# Decoder_ROMS.net
KiCad netlist of a schematic drawn in EAGLE
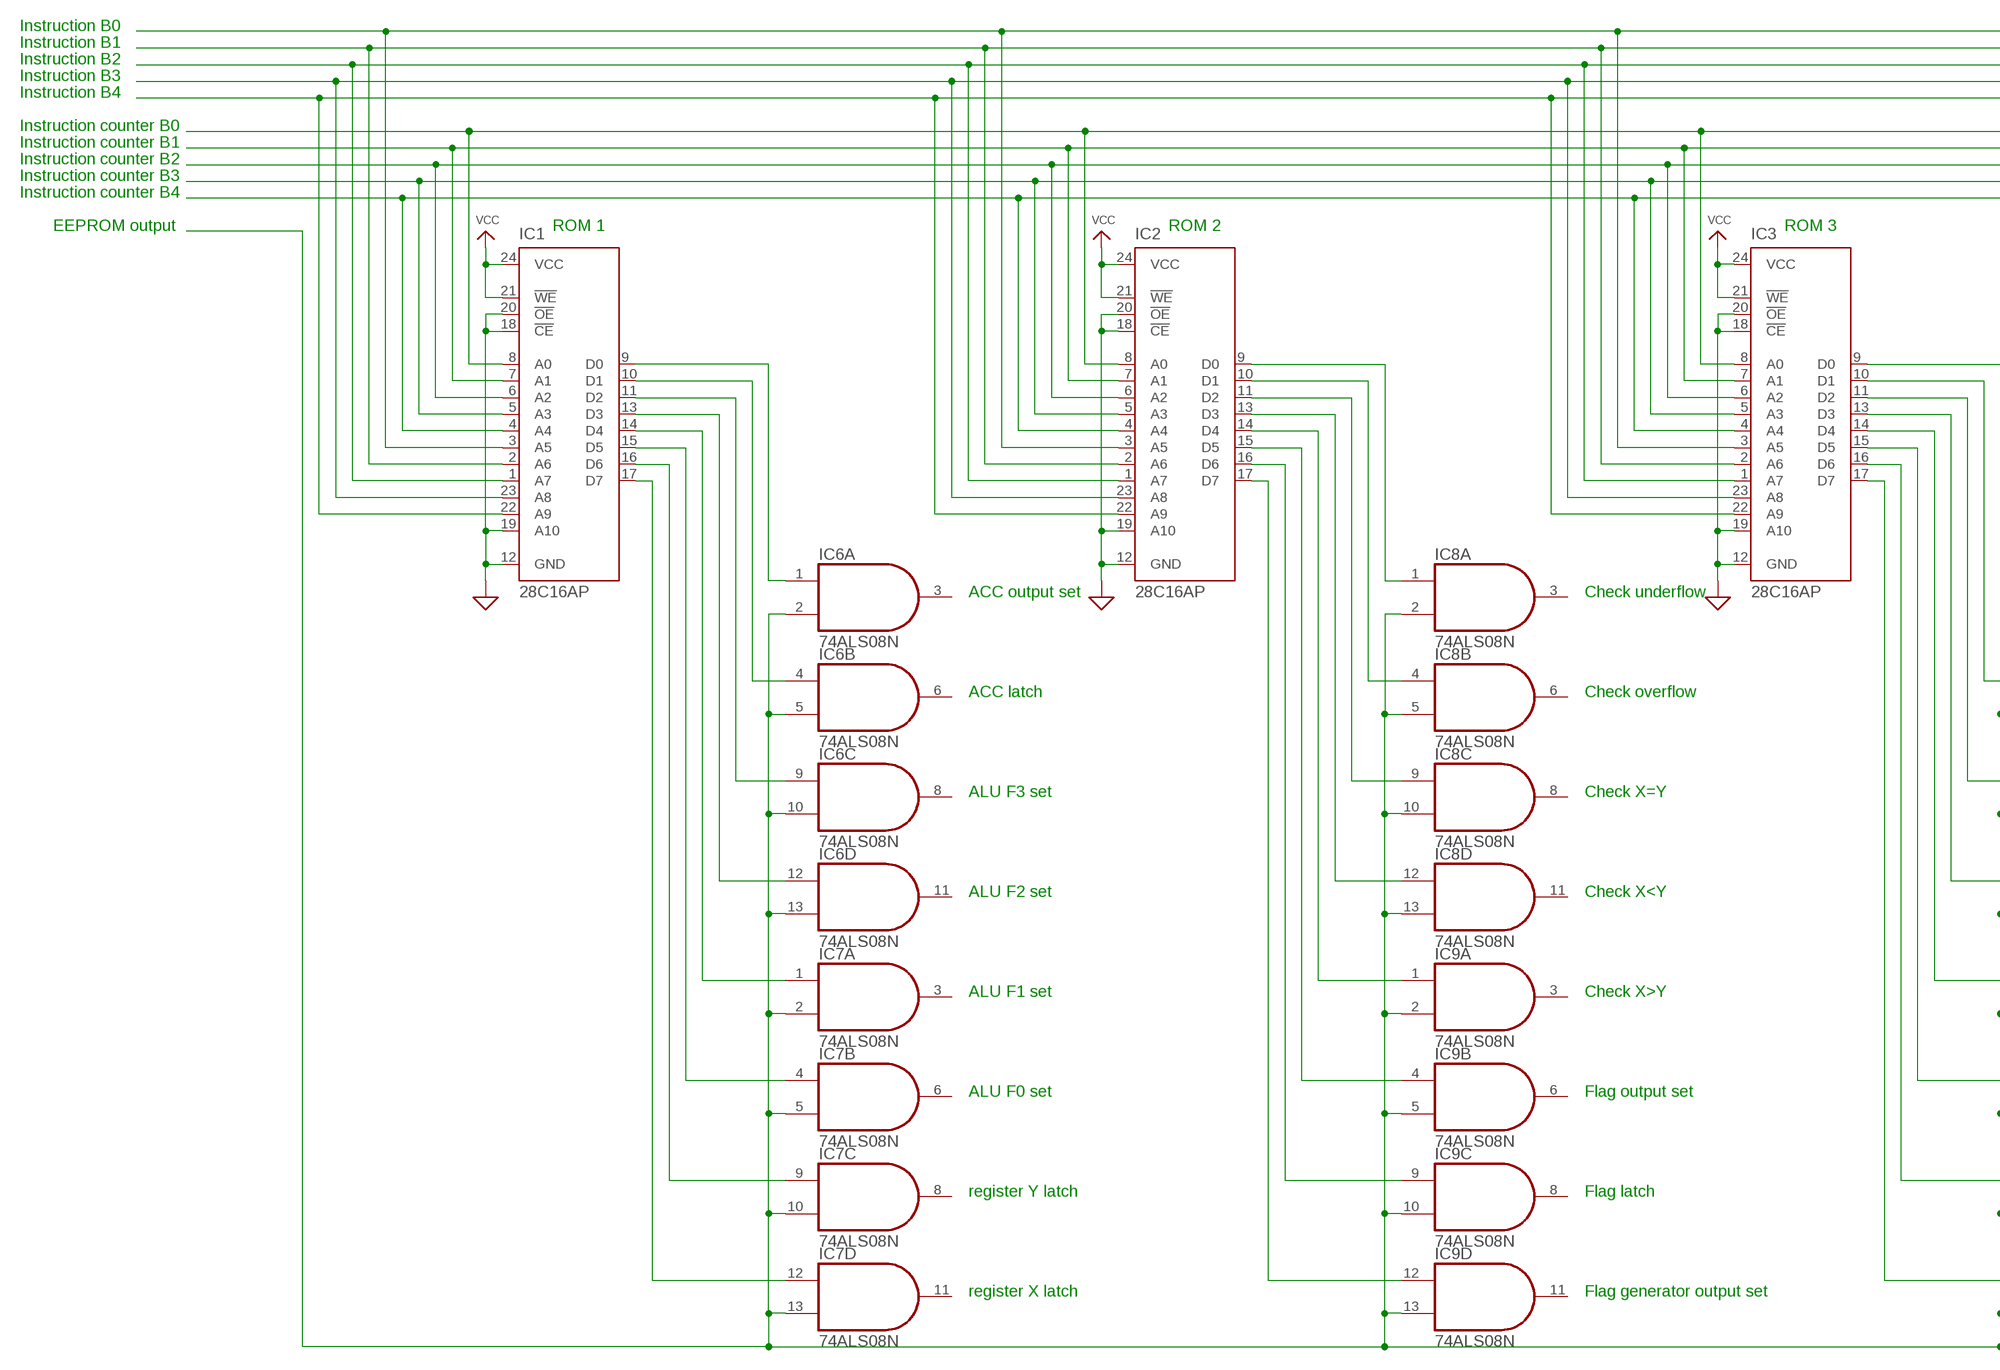
[diagram p0: schematic, sheet 1, part 1 of 2]
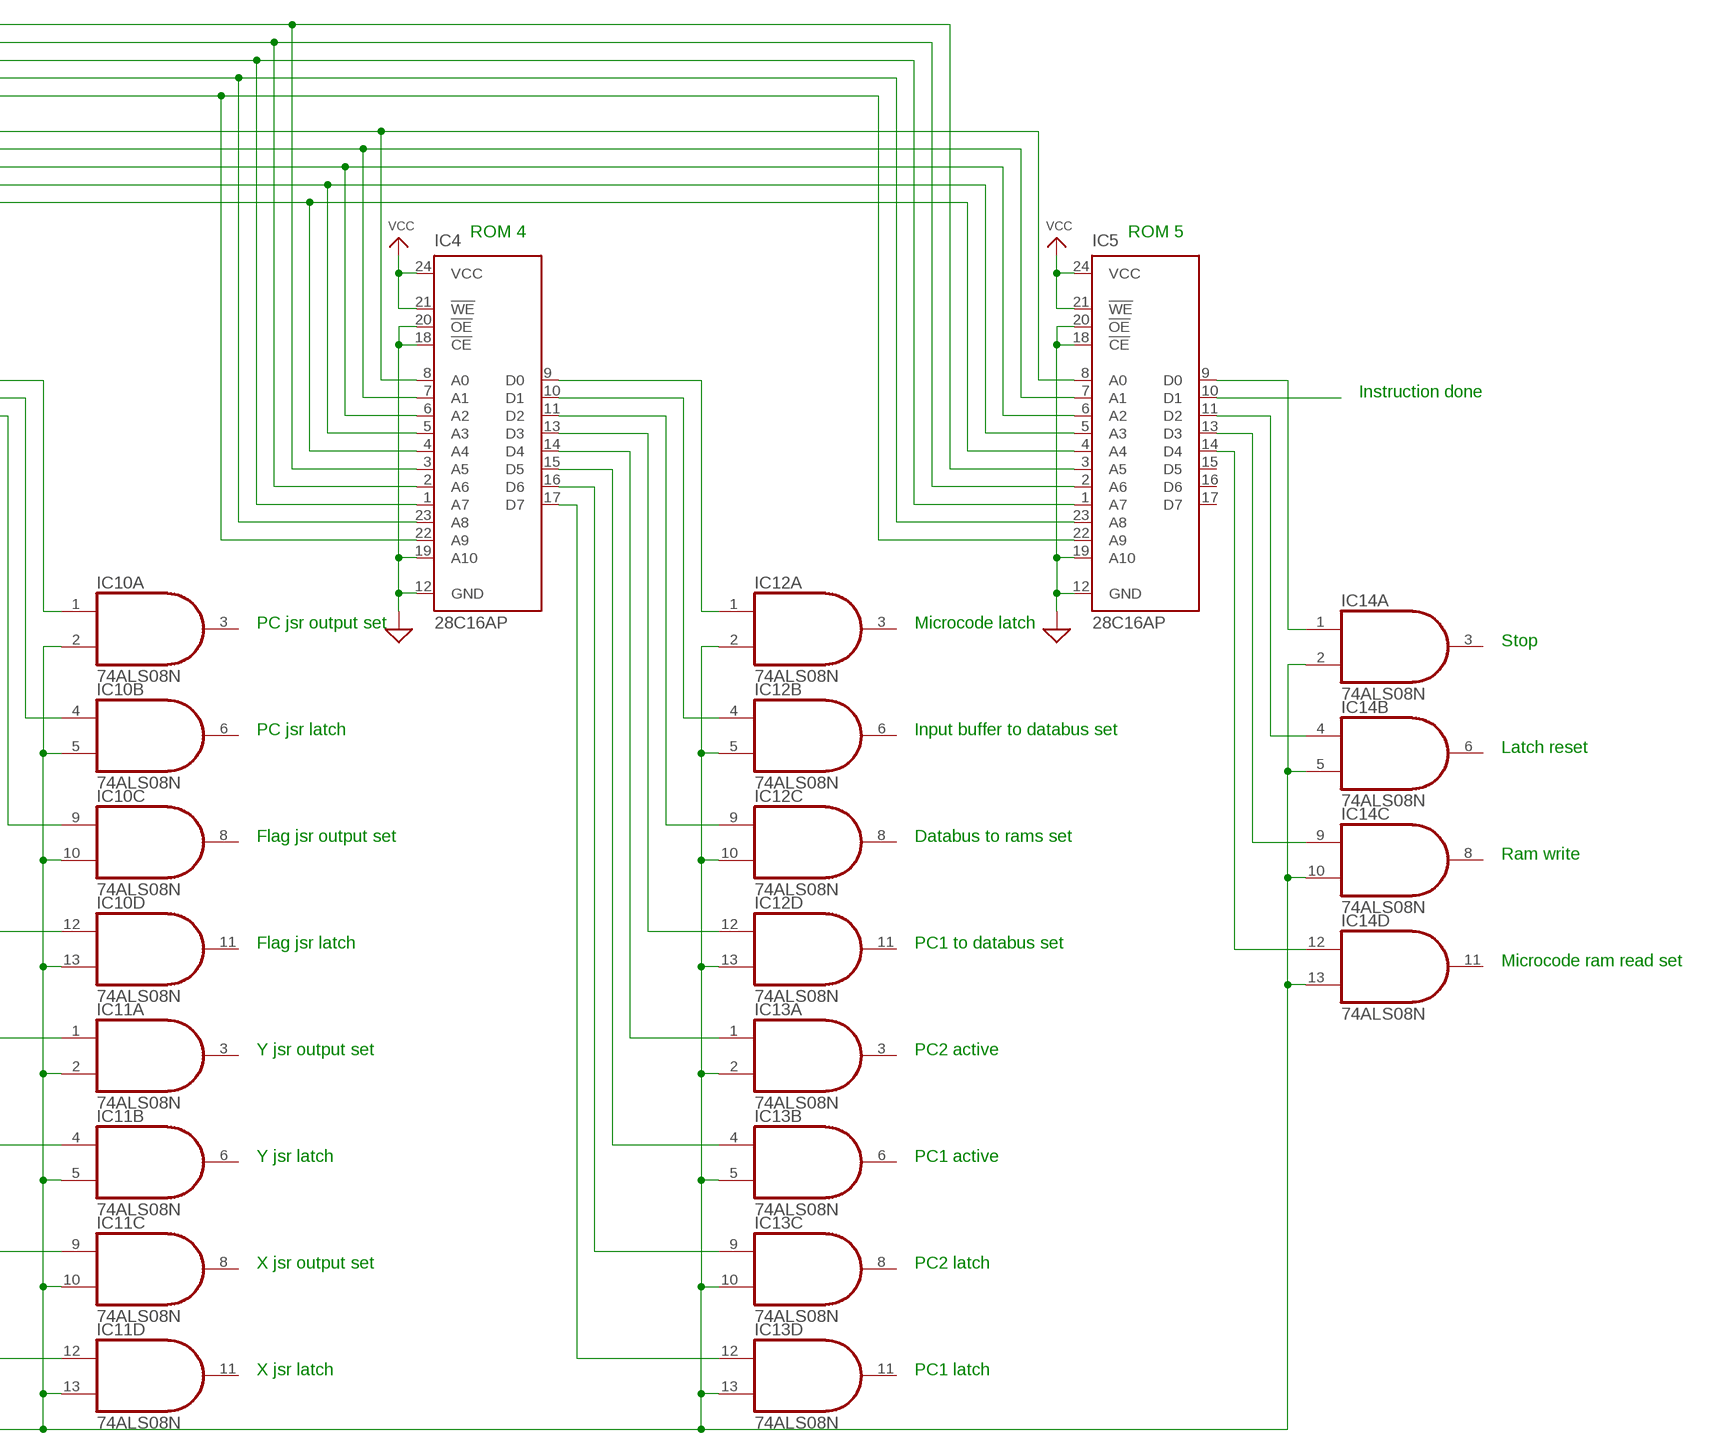
[diagram p1: schematic, sheet 1, part 2 of 2]

(export (version "E")
  (design (tool "Eeschema 10.0.6"))
  (components
    (comp (ref "IC1")
      (value "28C16AP")
      (footprint "eagle-import:DIL24-6")
      (fields (field (name "MPN") "CAT28C16ALI-12"))
      (libsource (lib "eagle-import") (part "2816APC"))
    )
    (comp (ref "IC2")
      (value "28C16AP")
      (footprint "eagle-import:DIL24-6")
      (fields (field (name "MPN") "CAT28C16ALI-12"))
      (libsource (lib "eagle-import") (part "2816APC"))
    )
    (comp (ref "IC3")
      (value "28C16AP")
      (footprint "eagle-import:DIL24-6")
      (fields (field (name "MPN") "CAT28C16ALI-12"))
      (libsource (lib "eagle-import") (part "2816APC"))
    )
    (comp (ref "IC4")
      (value "28C16AP")
      (footprint "eagle-import:DIL24-6")
      (fields (field (name "MPN") "CAT28C16ALI-12"))
      (libsource (lib "eagle-import") (part "2816APC"))
    )
    (comp (ref "IC5")
      (value "28C16AP")
      (footprint "eagle-import:DIL24-6")
      (fields (field (name "MPN") "CAT28C16ALI-12"))
      (libsource (lib "eagle-import") (part "2816APC"))
    )
    (comp (ref "IC6")
      (value "74ALS08N")
      (footprint "eagle-import:DIL14")
      (libsource (lib "eagle-import") (part "7408NALS"))
    )
    (comp (ref "IC7")
      (value "74ALS08N")
      (footprint "eagle-import:DIL14")
      (libsource (lib "eagle-import") (part "7408NALS"))
    )
    (comp (ref "IC8")
      (value "74ALS08N")
      (footprint "eagle-import:DIL14")
      (libsource (lib "eagle-import") (part "7408NALS"))
    )
    (comp (ref "IC9")
      (value "74ALS08N")
      (footprint "eagle-import:DIL14")
      (libsource (lib "eagle-import") (part "7408NALS"))
    )
    (comp (ref "IC10")
      (value "74ALS08N")
      (footprint "eagle-import:DIL14")
      (libsource (lib "eagle-import") (part "7408NALS"))
    )
    (comp (ref "IC11")
      (value "74ALS08N")
      (footprint "eagle-import:DIL14")
      (libsource (lib "eagle-import") (part "7408NALS"))
    )
    (comp (ref "IC12")
      (value "74ALS08N")
      (footprint "eagle-import:DIL14")
      (libsource (lib "eagle-import") (part "7408NALS"))
    )
    (comp (ref "IC13")
      (value "74ALS08N")
      (footprint "eagle-import:DIL14")
      (libsource (lib "eagle-import") (part "7408NALS"))
    )
    (comp (ref "IC14")
      (value "74ALS08N")
      (footprint "eagle-import:DIL14")
      (libsource (lib "eagle-import") (part "7408NALS"))
    )
  )
  (nets
    (net (code "1") (name "Net-(IC1-A0)") (class "Default")
      (node (ref "IC1") (pin "8") (pinfunction "A0_8") (pintype "input"))
      (node (ref "IC2") (pin "8") (pinfunction "A0_8") (pintype "input"))
      (node (ref "IC3") (pin "8") (pinfunction "A0_8") (pintype "input"))
      (node (ref "IC4") (pin "8") (pinfunction "A0_8") (pintype "input"))
      (node (ref "IC5") (pin "8") (pinfunction "A0_8") (pintype "input"))
    )
    (net (code "2") (name "Net-(IC1-A1)") (class "Default")
      (node (ref "IC1") (pin "7") (pinfunction "A1_7") (pintype "input"))
      (node (ref "IC2") (pin "7") (pinfunction "A1_7") (pintype "input"))
      (node (ref "IC3") (pin "7") (pinfunction "A1_7") (pintype "input"))
      (node (ref "IC4") (pin "7") (pinfunction "A1_7") (pintype "input"))
      (node (ref "IC5") (pin "7") (pinfunction "A1_7") (pintype "input"))
    )
    (net (code "3") (name "Net-(IC1-A2)") (class "Default")
      (node (ref "IC1") (pin "6") (pinfunction "A2_6") (pintype "input"))
      (node (ref "IC2") (pin "6") (pinfunction "A2_6") (pintype "input"))
      (node (ref "IC3") (pin "6") (pinfunction "A2_6") (pintype "input"))
      (node (ref "IC4") (pin "6") (pinfunction "A2_6") (pintype "input"))
      (node (ref "IC5") (pin "6") (pinfunction "A2_6") (pintype "input"))
    )
    (net (code "4") (name "Net-(IC1-A3)") (class "Default")
      (node (ref "IC1") (pin "5") (pinfunction "A3_5") (pintype "input"))
      (node (ref "IC2") (pin "5") (pinfunction "A3_5") (pintype "input"))
      (node (ref "IC3") (pin "5") (pinfunction "A3_5") (pintype "input"))
      (node (ref "IC4") (pin "5") (pinfunction "A3_5") (pintype "input"))
      (node (ref "IC5") (pin "5") (pinfunction "A3_5") (pintype "input"))
    )
    (net (code "5") (name "Net-(IC1-A4)") (class "Default")
      (node (ref "IC1") (pin "4") (pinfunction "A4_4") (pintype "input"))
      (node (ref "IC2") (pin "4") (pinfunction "A4_4") (pintype "input"))
      (node (ref "IC3") (pin "4") (pinfunction "A4_4") (pintype "input"))
      (node (ref "IC4") (pin "4") (pinfunction "A4_4") (pintype "input"))
      (node (ref "IC5") (pin "4") (pinfunction "A4_4") (pintype "input"))
    )
    (net (code "6") (name "Net-(IC1-A5)") (class "Default")
      (node (ref "IC1") (pin "3") (pinfunction "A5_3") (pintype "input"))
      (node (ref "IC2") (pin "3") (pinfunction "A5_3") (pintype "input"))
      (node (ref "IC3") (pin "3") (pinfunction "A5_3") (pintype "input"))
      (node (ref "IC4") (pin "3") (pinfunction "A5_3") (pintype "input"))
      (node (ref "IC5") (pin "3") (pinfunction "A5_3") (pintype "input"))
    )
    (net (code "7") (name "Net-(IC1-A6)") (class "Default")
      (node (ref "IC1") (pin "2") (pinfunction "A6_2") (pintype "input"))
      (node (ref "IC2") (pin "2") (pinfunction "A6_2") (pintype "input"))
      (node (ref "IC3") (pin "2") (pinfunction "A6_2") (pintype "input"))
      (node (ref "IC4") (pin "2") (pinfunction "A6_2") (pintype "input"))
      (node (ref "IC5") (pin "2") (pinfunction "A6_2") (pintype "input"))
    )
    (net (code "8") (name "Net-(IC1-A7)") (class "Default")
      (node (ref "IC1") (pin "1") (pinfunction "A7_1") (pintype "input"))
      (node (ref "IC2") (pin "1") (pinfunction "A7_1") (pintype "input"))
      (node (ref "IC3") (pin "1") (pinfunction "A7_1") (pintype "input"))
      (node (ref "IC4") (pin "1") (pinfunction "A7_1") (pintype "input"))
      (node (ref "IC5") (pin "1") (pinfunction "A7_1") (pintype "input"))
    )
    (net (code "9") (name "Net-(IC1-A8)") (class "Default")
      (node (ref "IC1") (pin "23") (pinfunction "A8_23") (pintype "input"))
      (node (ref "IC2") (pin "23") (pinfunction "A8_23") (pintype "input"))
      (node (ref "IC3") (pin "23") (pinfunction "A8_23") (pintype "input"))
      (node (ref "IC4") (pin "23") (pinfunction "A8_23") (pintype "input"))
      (node (ref "IC5") (pin "23") (pinfunction "A8_23") (pintype "input"))
    )
    (net (code "10") (name "Net-(IC1-A9)") (class "Default")
      (node (ref "IC1") (pin "22") (pinfunction "A9_22") (pintype "input"))
      (node (ref "IC2") (pin "22") (pinfunction "A9_22") (pintype "input"))
      (node (ref "IC3") (pin "22") (pinfunction "A9_22") (pintype "input"))
      (node (ref "IC4") (pin "22") (pinfunction "A9_22") (pintype "input"))
      (node (ref "IC5") (pin "22") (pinfunction "A9_22") (pintype "input"))
    )
    (net (code "11") (name "Net-(IC1-D0)") (class "Default")
      (node (ref "IC1") (pin "9") (pinfunction "D0_9") (pintype "tri_state"))
      (node (ref "IC6") (pin "1") (pinfunction "I0_1") (pintype "input"))
    )
    (net (code "12") (name "Net-(IC1-D1)") (class "Default")
      (node (ref "IC1") (pin "10") (pinfunction "D1_10") (pintype "tri_state"))
      (node (ref "IC6") (pin "4") (pinfunction "I0_4") (pintype "input"))
    )
    (net (code "13") (name "Net-(IC1-D2)") (class "Default")
      (node (ref "IC1") (pin "11") (pinfunction "D2_11") (pintype "tri_state"))
      (node (ref "IC6") (pin "9") (pinfunction "I0_9") (pintype "input"))
    )
    (net (code "14") (name "Net-(IC1-D3)") (class "Default")
      (node (ref "IC1") (pin "13") (pinfunction "D3_13") (pintype "tri_state"))
      (node (ref "IC6") (pin "12") (pinfunction "I0_12") (pintype "input"))
    )
    (net (code "15") (name "Net-(IC1-D4)") (class "Default")
      (node (ref "IC1") (pin "14") (pinfunction "D4_14") (pintype "tri_state"))
      (node (ref "IC7") (pin "1") (pinfunction "I0_1") (pintype "input"))
    )
    (net (code "16") (name "Net-(IC1-D5)") (class "Default")
      (node (ref "IC1") (pin "15") (pinfunction "D5_15") (pintype "tri_state"))
      (node (ref "IC7") (pin "4") (pinfunction "I0_4") (pintype "input"))
    )
    (net (code "17") (name "Net-(IC1-D6)") (class "Default")
      (node (ref "IC1") (pin "16") (pinfunction "D6_16") (pintype "tri_state"))
      (node (ref "IC7") (pin "9") (pinfunction "I0_9") (pintype "input"))
    )
    (net (code "18") (name "Net-(IC1-D7)") (class "Default")
      (node (ref "IC1") (pin "17") (pinfunction "D7_17") (pintype "tri_state"))
      (node (ref "IC7") (pin "12") (pinfunction "I0_12") (pintype "input"))
    )
    (net (code "19") (name "Net-(IC2-D0)") (class "Default")
      (node (ref "IC2") (pin "9") (pinfunction "D0_9") (pintype "tri_state"))
      (node (ref "IC8") (pin "1") (pinfunction "I0_1") (pintype "input"))
    )
    (net (code "20") (name "Net-(IC2-D1)") (class "Default")
      (node (ref "IC2") (pin "10") (pinfunction "D1_10") (pintype "tri_state"))
      (node (ref "IC8") (pin "4") (pinfunction "I0_4") (pintype "input"))
    )
    (net (code "21") (name "Net-(IC2-D2)") (class "Default")
      (node (ref "IC2") (pin "11") (pinfunction "D2_11") (pintype "tri_state"))
      (node (ref "IC8") (pin "9") (pinfunction "I0_9") (pintype "input"))
    )
    (net (code "22") (name "Net-(IC2-D3)") (class "Default")
      (node (ref "IC2") (pin "13") (pinfunction "D3_13") (pintype "tri_state"))
      (node (ref "IC8") (pin "12") (pinfunction "I0_12") (pintype "input"))
    )
    (net (code "23") (name "Net-(IC2-D4)") (class "Default")
      (node (ref "IC2") (pin "14") (pinfunction "D4_14") (pintype "tri_state"))
      (node (ref "IC9") (pin "1") (pinfunction "I0_1") (pintype "input"))
    )
    (net (code "24") (name "Net-(IC2-D5)") (class "Default")
      (node (ref "IC2") (pin "15") (pinfunction "D5_15") (pintype "tri_state"))
      (node (ref "IC9") (pin "4") (pinfunction "I0_4") (pintype "input"))
    )
    (net (code "25") (name "Net-(IC2-D6)") (class "Default")
      (node (ref "IC2") (pin "16") (pinfunction "D6_16") (pintype "tri_state"))
      (node (ref "IC9") (pin "9") (pinfunction "I0_9") (pintype "input"))
    )
    (net (code "26") (name "Net-(IC2-D7)") (class "Default")
      (node (ref "IC2") (pin "17") (pinfunction "D7_17") (pintype "tri_state"))
      (node (ref "IC9") (pin "12") (pinfunction "I0_12") (pintype "input"))
    )
    (net (code "27") (name "Net-(IC10A-I0)") (class "Default")
      (node (ref "IC10") (pin "1") (pinfunction "I0_1") (pintype "input"))
      (node (ref "IC3") (pin "9") (pinfunction "D0_9") (pintype "tri_state"))
    )
    (net (code "28") (name "Net-(IC10A-I1)") (class "Default")
      (node (ref "IC10") (pin "10") (pinfunction "I1_10") (pintype "input"))
      (node (ref "IC10") (pin "13") (pinfunction "I1_13") (pintype "input"))
      (node (ref "IC10") (pin "2") (pinfunction "I1_2") (pintype "input"))
      (node (ref "IC10") (pin "5") (pinfunction "I1_5") (pintype "input"))
      (node (ref "IC11") (pin "10") (pinfunction "I1_10") (pintype "input"))
      (node (ref "IC11") (pin "13") (pinfunction "I1_13") (pintype "input"))
      (node (ref "IC11") (pin "2") (pinfunction "I1_2") (pintype "input"))
      (node (ref "IC11") (pin "5") (pinfunction "I1_5") (pintype "input"))
      (node (ref "IC12") (pin "10") (pinfunction "I1_10") (pintype "input"))
      (node (ref "IC12") (pin "13") (pinfunction "I1_13") (pintype "input"))
      (node (ref "IC12") (pin "2") (pinfunction "I1_2") (pintype "input"))
      (node (ref "IC12") (pin "5") (pinfunction "I1_5") (pintype "input"))
      (node (ref "IC13") (pin "10") (pinfunction "I1_10") (pintype "input"))
      (node (ref "IC13") (pin "13") (pinfunction "I1_13") (pintype "input"))
      (node (ref "IC13") (pin "2") (pinfunction "I1_2") (pintype "input"))
      (node (ref "IC13") (pin "5") (pinfunction "I1_5") (pintype "input"))
      (node (ref "IC14") (pin "10") (pinfunction "I1_10") (pintype "input"))
      (node (ref "IC14") (pin "13") (pinfunction "I1_13") (pintype "input"))
      (node (ref "IC14") (pin "2") (pinfunction "I1_2") (pintype "input"))
      (node (ref "IC14") (pin "5") (pinfunction "I1_5") (pintype "input"))
      (node (ref "IC6") (pin "10") (pinfunction "I1_10") (pintype "input"))
      (node (ref "IC6") (pin "13") (pinfunction "I1_13") (pintype "input"))
      (node (ref "IC6") (pin "2") (pinfunction "I1_2") (pintype "input"))
      (node (ref "IC6") (pin "5") (pinfunction "I1_5") (pintype "input"))
      (node (ref "IC7") (pin "10") (pinfunction "I1_10") (pintype "input"))
      (node (ref "IC7") (pin "13") (pinfunction "I1_13") (pintype "input"))
      (node (ref "IC7") (pin "2") (pinfunction "I1_2") (pintype "input"))
      (node (ref "IC7") (pin "5") (pinfunction "I1_5") (pintype "input"))
      (node (ref "IC8") (pin "10") (pinfunction "I1_10") (pintype "input"))
      (node (ref "IC8") (pin "13") (pinfunction "I1_13") (pintype "input"))
      (node (ref "IC8") (pin "2") (pinfunction "I1_2") (pintype "input"))
      (node (ref "IC8") (pin "5") (pinfunction "I1_5") (pintype "input"))
      (node (ref "IC9") (pin "10") (pinfunction "I1_10") (pintype "input"))
      (node (ref "IC9") (pin "13") (pinfunction "I1_13") (pintype "input"))
      (node (ref "IC9") (pin "2") (pinfunction "I1_2") (pintype "input"))
      (node (ref "IC9") (pin "5") (pinfunction "I1_5") (pintype "input"))
    )
    (net (code "29") (name "Net-(IC10B-I0)") (class "Default")
      (node (ref "IC10") (pin "4") (pinfunction "I0_4") (pintype "input"))
      (node (ref "IC3") (pin "10") (pinfunction "D1_10") (pintype "tri_state"))
    )
    (net (code "30") (name "Net-(IC10C-I0)") (class "Default")
      (node (ref "IC10") (pin "9") (pinfunction "I0_9") (pintype "input"))
      (node (ref "IC3") (pin "11") (pinfunction "D2_11") (pintype "tri_state"))
    )
    (net (code "31") (name "Net-(IC10D-I0)") (class "Default")
      (node (ref "IC10") (pin "12") (pinfunction "I0_12") (pintype "input"))
      (node (ref "IC3") (pin "13") (pinfunction "D3_13") (pintype "tri_state"))
    )
    (net (code "32") (name "Net-(IC11A-I0)") (class "Default")
      (node (ref "IC11") (pin "1") (pinfunction "I0_1") (pintype "input"))
      (node (ref "IC3") (pin "14") (pinfunction "D4_14") (pintype "tri_state"))
    )
    (net (code "33") (name "Net-(IC11B-I0)") (class "Default")
      (node (ref "IC11") (pin "4") (pinfunction "I0_4") (pintype "input"))
      (node (ref "IC3") (pin "15") (pinfunction "D5_15") (pintype "tri_state"))
    )
    (net (code "34") (name "Net-(IC11C-I0)") (class "Default")
      (node (ref "IC11") (pin "9") (pinfunction "I0_9") (pintype "input"))
      (node (ref "IC3") (pin "16") (pinfunction "D6_16") (pintype "tri_state"))
    )
    (net (code "35") (name "Net-(IC11D-I0)") (class "Default")
      (node (ref "IC11") (pin "12") (pinfunction "I0_12") (pintype "input"))
      (node (ref "IC3") (pin "17") (pinfunction "D7_17") (pintype "tri_state"))
    )
    (net (code "36") (name "Net-(IC12A-I0)") (class "Default")
      (node (ref "IC12") (pin "1") (pinfunction "I0_1") (pintype "input"))
      (node (ref "IC4") (pin "9") (pinfunction "D0_9") (pintype "tri_state"))
    )
    (net (code "37") (name "Net-(IC12B-I0)") (class "Default")
      (node (ref "IC12") (pin "4") (pinfunction "I0_4") (pintype "input"))
      (node (ref "IC4") (pin "10") (pinfunction "D1_10") (pintype "tri_state"))
    )
    (net (code "38") (name "Net-(IC12C-I0)") (class "Default")
      (node (ref "IC12") (pin "9") (pinfunction "I0_9") (pintype "input"))
      (node (ref "IC4") (pin "11") (pinfunction "D2_11") (pintype "tri_state"))
    )
    (net (code "39") (name "Net-(IC12D-I0)") (class "Default")
      (node (ref "IC12") (pin "12") (pinfunction "I0_12") (pintype "input"))
      (node (ref "IC4") (pin "13") (pinfunction "D3_13") (pintype "tri_state"))
    )
    (net (code "40") (name "Net-(IC13A-I0)") (class "Default")
      (node (ref "IC13") (pin "1") (pinfunction "I0_1") (pintype "input"))
      (node (ref "IC4") (pin "14") (pinfunction "D4_14") (pintype "tri_state"))
    )
    (net (code "41") (name "Net-(IC13B-I0)") (class "Default")
      (node (ref "IC13") (pin "4") (pinfunction "I0_4") (pintype "input"))
      (node (ref "IC4") (pin "15") (pinfunction "D5_15") (pintype "tri_state"))
    )
    (net (code "42") (name "Net-(IC13C-I0)") (class "Default")
      (node (ref "IC13") (pin "9") (pinfunction "I0_9") (pintype "input"))
      (node (ref "IC4") (pin "16") (pinfunction "D6_16") (pintype "tri_state"))
    )
    (net (code "43") (name "Net-(IC13D-I0)") (class "Default")
      (node (ref "IC13") (pin "12") (pinfunction "I0_12") (pintype "input"))
      (node (ref "IC4") (pin "17") (pinfunction "D7_17") (pintype "tri_state"))
    )
    (net (code "44") (name "Net-(IC14A-I0)") (class "Default")
      (node (ref "IC14") (pin "1") (pinfunction "I0_1") (pintype "input"))
      (node (ref "IC5") (pin "9") (pinfunction "D0_9") (pintype "tri_state"))
    )
    (net (code "45") (name "Net-(IC14B-I0)") (class "Default")
      (node (ref "IC14") (pin "4") (pinfunction "I0_4") (pintype "input"))
      (node (ref "IC5") (pin "11") (pinfunction "D2_11") (pintype "tri_state"))
    )
    (net (code "46") (name "Net-(IC14C-I0)") (class "Default")
      (node (ref "IC14") (pin "9") (pinfunction "I0_9") (pintype "input"))
      (node (ref "IC5") (pin "13") (pinfunction "D3_13") (pintype "tri_state"))
    )
    (net (code "47") (name "Net-(IC14D-I0)") (class "Default")
      (node (ref "IC14") (pin "12") (pinfunction "I0_12") (pintype "input"))
      (node (ref "IC5") (pin "14") (pinfunction "D4_14") (pintype "tri_state"))
    )
    (net (code "48") (name "SUP") (class "Default")
      (node (ref "IC1") (pin "12") (pinfunction "GND_12") (pintype "power_in"))
      (node (ref "IC1") (pin "18") (pinfunction "~{CE}_18") (pintype "input"))
      (node (ref "IC1") (pin "19") (pinfunction "A10_19") (pintype "input"))
      (node (ref "IC1") (pin "20") (pinfunction "~{OE}_20") (pintype "input"))
      (node (ref "IC2") (pin "12") (pinfunction "GND_12") (pintype "power_in"))
      (node (ref "IC2") (pin "18") (pinfunction "~{CE}_18") (pintype "input"))
      (node (ref "IC2") (pin "19") (pinfunction "A10_19") (pintype "input"))
      (node (ref "IC2") (pin "20") (pinfunction "~{OE}_20") (pintype "input"))
      (node (ref "IC3") (pin "12") (pinfunction "GND_12") (pintype "power_in"))
      (node (ref "IC3") (pin "18") (pinfunction "~{CE}_18") (pintype "input"))
      (node (ref "IC3") (pin "19") (pinfunction "A10_19") (pintype "input"))
      (node (ref "IC3") (pin "20") (pinfunction "~{OE}_20") (pintype "input"))
      (node (ref "IC4") (pin "12") (pinfunction "GND_12") (pintype "power_in"))
      (node (ref "IC4") (pin "18") (pinfunction "~{CE}_18") (pintype "input"))
      (node (ref "IC4") (pin "19") (pinfunction "A10_19") (pintype "input"))
      (node (ref "IC4") (pin "20") (pinfunction "~{OE}_20") (pintype "input"))
      (node (ref "IC5") (pin "12") (pinfunction "GND_12") (pintype "power_in"))
      (node (ref "IC5") (pin "18") (pinfunction "~{CE}_18") (pintype "input"))
      (node (ref "IC5") (pin "19") (pinfunction "A10_19") (pintype "input"))
      (node (ref "IC5") (pin "20") (pinfunction "~{OE}_20") (pintype "input"))
    )
    (net (code "49") (name "VCC") (class "Default")
      (node (ref "IC1") (pin "21") (pinfunction "~{WE}_21") (pintype "input"))
      (node (ref "IC1") (pin "24") (pinfunction "VCC_24") (pintype "power_in"))
      (node (ref "IC2") (pin "21") (pinfunction "~{WE}_21") (pintype "input"))
      (node (ref "IC2") (pin "24") (pinfunction "VCC_24") (pintype "power_in"))
      (node (ref "IC3") (pin "21") (pinfunction "~{WE}_21") (pintype "input"))
      (node (ref "IC3") (pin "24") (pinfunction "VCC_24") (pintype "power_in"))
      (node (ref "IC4") (pin "21") (pinfunction "~{WE}_21") (pintype "input"))
      (node (ref "IC4") (pin "24") (pinfunction "VCC_24") (pintype "power_in"))
      (node (ref "IC5") (pin "21") (pinfunction "~{WE}_21") (pintype "input"))
      (node (ref "IC5") (pin "24") (pinfunction "VCC_24") (pintype "power_in"))
    )
    (net (code "50") (name "unconnected-(IC5-D1-Pad10)") (class "Default")
      (node (ref "IC5") (pin "10") (pinfunction "D1_10") (pintype "tri_state"))
    )
    (net (code "51") (name "unconnected-(IC5-D5-Pad15)") (class "Default")
      (node (ref "IC5") (pin "15") (pinfunction "D5_15") (pintype "tri_state"))
    )
    (net (code "52") (name "unconnected-(IC5-D6-Pad16)") (class "Default")
      (node (ref "IC5") (pin "16") (pinfunction "D6_16") (pintype "tri_state"))
    )
    (net (code "53") (name "unconnected-(IC5-D7-Pad17)") (class "Default")
      (node (ref "IC5") (pin "17") (pinfunction "D7_17") (pintype "tri_state"))
    )
    (net (code "54") (name "unconnected-(IC6A-O-Pad3)") (class "Default")
      (node (ref "IC6") (pin "3") (pinfunction "O_3") (pintype "output"))
    )
    (net (code "55") (name "unconnected-(IC6B-O-Pad6)") (class "Default")
      (node (ref "IC6") (pin "6") (pinfunction "O_6") (pintype "output"))
    )
    (net (code "56") (name "unconnected-(IC6C-O-Pad8)") (class "Default")
      (node (ref "IC6") (pin "8") (pinfunction "O_8") (pintype "output"))
    )
    (net (code "57") (name "unconnected-(IC6D-O-Pad11)") (class "Default")
      (node (ref "IC6") (pin "11") (pinfunction "O_11") (pintype "output"))
    )
    (net (code "58") (name "unconnected-(IC7A-O-Pad3)") (class "Default")
      (node (ref "IC7") (pin "3") (pinfunction "O_3") (pintype "output"))
    )
    (net (code "59") (name "unconnected-(IC7B-O-Pad6)") (class "Default")
      (node (ref "IC7") (pin "6") (pinfunction "O_6") (pintype "output"))
    )
    (net (code "60") (name "unconnected-(IC7C-O-Pad8)") (class "Default")
      (node (ref "IC7") (pin "8") (pinfunction "O_8") (pintype "output"))
    )
    (net (code "61") (name "unconnected-(IC7D-O-Pad11)") (class "Default")
      (node (ref "IC7") (pin "11") (pinfunction "O_11") (pintype "output"))
    )
    (net (code "62") (name "unconnected-(IC8A-O-Pad3)") (class "Default")
      (node (ref "IC8") (pin "3") (pinfunction "O_3") (pintype "output"))
    )
    (net (code "63") (name "unconnected-(IC8B-O-Pad6)") (class "Default")
      (node (ref "IC8") (pin "6") (pinfunction "O_6") (pintype "output"))
    )
    (net (code "64") (name "unconnected-(IC8C-O-Pad8)") (class "Default")
      (node (ref "IC8") (pin "8") (pinfunction "O_8") (pintype "output"))
    )
    (net (code "65") (name "unconnected-(IC8D-O-Pad11)") (class "Default")
      (node (ref "IC8") (pin "11") (pinfunction "O_11") (pintype "output"))
    )
    (net (code "66") (name "unconnected-(IC9A-O-Pad3)") (class "Default")
      (node (ref "IC9") (pin "3") (pinfunction "O_3") (pintype "output"))
    )
    (net (code "67") (name "unconnected-(IC9B-O-Pad6)") (class "Default")
      (node (ref "IC9") (pin "6") (pinfunction "O_6") (pintype "output"))
    )
    (net (code "68") (name "unconnected-(IC9C-O-Pad8)") (class "Default")
      (node (ref "IC9") (pin "8") (pinfunction "O_8") (pintype "output"))
    )
    (net (code "69") (name "unconnected-(IC9D-O-Pad11)") (class "Default")
      (node (ref "IC9") (pin "11") (pinfunction "O_11") (pintype "output"))
    )
    (net (code "70") (name "unconnected-(IC10A-O-Pad3)") (class "Default")
      (node (ref "IC10") (pin "3") (pinfunction "O_3") (pintype "output"))
    )
    (net (code "71") (name "unconnected-(IC10B-O-Pad6)") (class "Default")
      (node (ref "IC10") (pin "6") (pinfunction "O_6") (pintype "output"))
    )
    (net (code "72") (name "unconnected-(IC10C-O-Pad8)") (class "Default")
      (node (ref "IC10") (pin "8") (pinfunction "O_8") (pintype "output"))
    )
    (net (code "73") (name "unconnected-(IC10D-O-Pad11)") (class "Default")
      (node (ref "IC10") (pin "11") (pinfunction "O_11") (pintype "output"))
    )
    (net (code "74") (name "unconnected-(IC11A-O-Pad3)") (class "Default")
      (node (ref "IC11") (pin "3") (pinfunction "O_3") (pintype "output"))
    )
    (net (code "75") (name "unconnected-(IC11B-O-Pad6)") (class "Default")
      (node (ref "IC11") (pin "6") (pinfunction "O_6") (pintype "output"))
    )
    (net (code "76") (name "unconnected-(IC11C-O-Pad8)") (class "Default")
      (node (ref "IC11") (pin "8") (pinfunction "O_8") (pintype "output"))
    )
    (net (code "77") (name "unconnected-(IC11D-O-Pad11)") (class "Default")
      (node (ref "IC11") (pin "11") (pinfunction "O_11") (pintype "output"))
    )
    (net (code "78") (name "unconnected-(IC12A-O-Pad3)") (class "Default")
      (node (ref "IC12") (pin "3") (pinfunction "O_3") (pintype "output"))
    )
    (net (code "79") (name "unconnected-(IC12B-O-Pad6)") (class "Default")
      (node (ref "IC12") (pin "6") (pinfunction "O_6") (pintype "output"))
    )
    (net (code "80") (name "unconnected-(IC12C-O-Pad8)") (class "Default")
      (node (ref "IC12") (pin "8") (pinfunction "O_8") (pintype "output"))
    )
    (net (code "81") (name "unconnected-(IC12D-O-Pad11)") (class "Default")
      (node (ref "IC12") (pin "11") (pinfunction "O_11") (pintype "output"))
    )
    (net (code "82") (name "unconnected-(IC13A-O-Pad3)") (class "Default")
      (node (ref "IC13") (pin "3") (pinfunction "O_3") (pintype "output"))
    )
    (net (code "83") (name "unconnected-(IC13B-O-Pad6)") (class "Default")
      (node (ref "IC13") (pin "6") (pinfunction "O_6") (pintype "output"))
    )
    (net (code "84") (name "unconnected-(IC13C-O-Pad8)") (class "Default")
      (node (ref "IC13") (pin "8") (pinfunction "O_8") (pintype "output"))
    )
    (net (code "85") (name "unconnected-(IC13D-O-Pad11)") (class "Default")
      (node (ref "IC13") (pin "11") (pinfunction "O_11") (pintype "output"))
    )
    (net (code "86") (name "unconnected-(IC14A-O-Pad3)") (class "Default")
      (node (ref "IC14") (pin "3") (pinfunction "O_3") (pintype "output"))
    )
    (net (code "87") (name "unconnected-(IC14B-O-Pad6)") (class "Default")
      (node (ref "IC14") (pin "6") (pinfunction "O_6") (pintype "output"))
    )
    (net (code "88") (name "unconnected-(IC14C-O-Pad8)") (class "Default")
      (node (ref "IC14") (pin "8") (pinfunction "O_8") (pintype "output"))
    )
    (net (code "89") (name "unconnected-(IC14D-O-Pad11)") (class "Default")
      (node (ref "IC14") (pin "11") (pinfunction "O_11") (pintype "output"))
    )
  )
)
